# PDB_Supply.net
KiCad netlist of a schematic drawn in Altium Designer
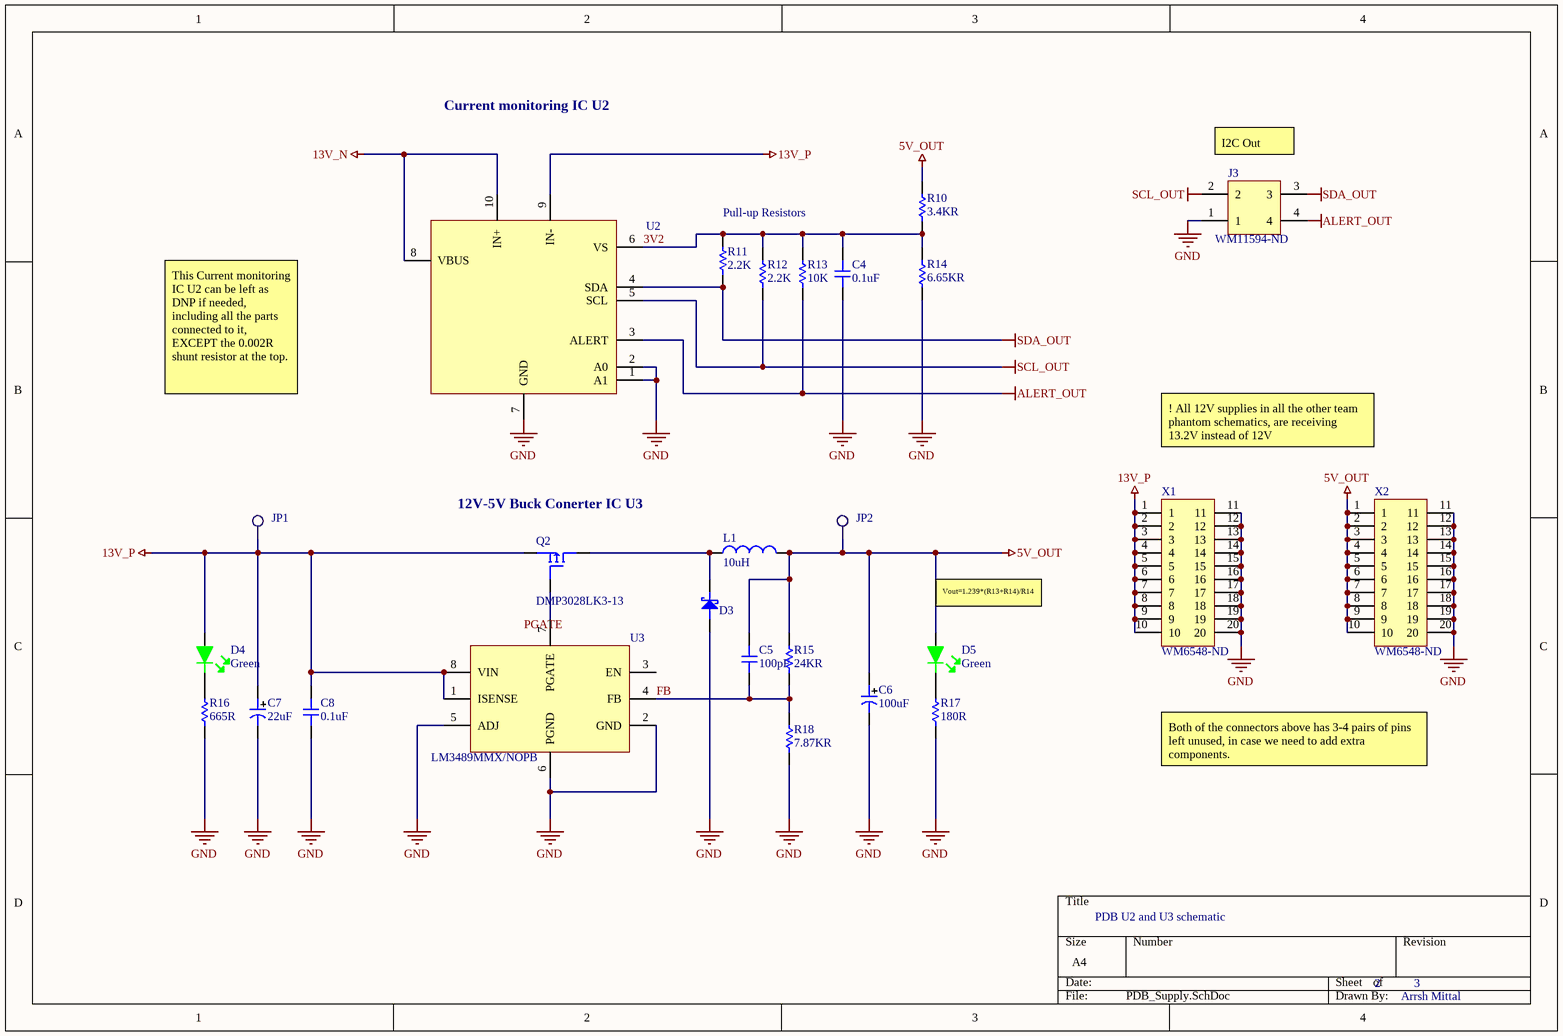
[diagram p0: PDB_Supply.SchDoc]

(export (version "E")
  (design (tool "Eeschema 10.0.6"))
  (components
    (comp (ref "C4")
      (value "0.1uF")
      (footprint "CAP-0805")
      (description "CAP CER 0.1UF 16V Y5V 0805")
      (fields
        (field (name "MANUFACTURER") "KEMET")
        (field (name "MANUFACTURER PART NUMBER") "C0805C104Z4VACTU")
      )
      (libsource (lib "Capacitors") (part "0805-0.1uF-16V"))
    )
    (comp (ref "C5")
      (value "100pF")
      (footprint "CAP-0603")
      (description "0603 100 pF 50 V ±5% Tolerance C0G/NP0 SMT Multilayer Ceramic Capacitor")
      (fields
        (field (name "MANUFACTURER") "Kyocera AVX")
        (field (name "MANUFACTURER PART NUMBER") "06035A101JAT2~{A}4K")
      )
      (libsource (lib "Capacitors") (part "0603-100pF-50V"))
    )
    (comp (ref "C6")
      (value "100uF")
      (footprint "CAPMP7343X31N 2917 Tantilum Cap")
      (fields
        (field (name "MANUFACTURER") "KEMET")
        (field (name "MANUFACTURER PART NUMBER") "T591D107M010ATE080")
        (field (name "TOLERANCE") "20%")
      )
      (libsource (lib "Capacitors") (part "2917-100uF Tantalum Cap"))
    )
    (comp (ref "C7")
      (value "22uF")
      (footprint "CAPAE7366X55M")
      (description "Aluminum Electrolytic Capacitors - SMD 22uF 50 Volts 20% LYTICS/IC")
      (fields
        (field (name "MANUFACTURER") "CDE Illinois Capacitor")
        (field (name "MANUFACTURER PART NUMBER") "226SML050M")
      )
      (libsource (lib "Capacitors") (part "AEC-22uF-50V"))
    )
    (comp (ref "C8")
      (value "0.1uF")
      (footprint "CAP-0805")
      (description "CAP CER 0.1UF 50V Y5V 0805")
      (fields
        (field (name "MANUFACTURER") "KEMET")
        (field (name "MANUFACTURER PART NUMBER") "C0805C104Z5VACTU")
      )
      (libsource (lib "Capacitors") (part "0805-0.1uF-50V"))
    )
    (comp (ref "D3")
      (value "40V")
      (footprint "DO-214AB (SMC)")
      (description "DIODE SCHOTTKY 40V 8A DO214AB")
      (fields (field (name "MANUFACTURER") "MCC") (field (name "MANUFACTURER PART NUMBER") "SK84L-TP"))
      (libsource (lib "Diodes") (part "Schottky-40V-8A"))
    )
    (comp (ref "D4")
      (value "Green")
      (footprint "LED-0603")
      (description "LED GREEN CLEAR 0603 SMD")
      (fields
        (field (name "MANUFACTURER") "Wurth Electronics")
        (field (name "MANUFACTURER PART NUMBER") "150060VS75000")
      )
      (libsource (lib "LEDs") (part "LED-Green"))
    )
    (comp (ref "D5")
      (value "Green")
      (footprint "LED-0603")
      (description "LED GREEN CLEAR 0603 SMD")
      (fields
        (field (name "MANUFACTURER") "Wurth Electronics")
        (field (name "MANUFACTURER PART NUMBER") "150060VS75000")
      )
      (libsource (lib "LEDs") (part "LED-Green"))
    )
    (comp (ref "J3")
      (value "WM11594-ND")
      (footprint "2X2PIN")
      (description "CONN HEADER R/A 4POS 3.5MM")
      (fields (field (name "MANUFACTURER") "Molex") (field (name "MANUFACTURER PART NUMBER") "172316-1104"))
      (libsource (lib "Connectors") (part "2X2PIN"))
    )
    (comp (ref "JP1")
      (value "Testpoint2")
      (footprint "TP2")
      (description "Single layer pad TP")
      (libsource (lib "Misc") (part "Testpoint2"))
    )
    (comp (ref "JP2")
      (value "Testpoint2")
      (footprint "TP2")
      (description "Single layer pad TP")
      (libsource (lib "Misc") (part "Testpoint2"))
    )
    (comp (ref "L1")
      (value "10uH")
      (footprint "PQ2614BLA-100K footprint")
      (description "Inductor Power Shielded Wirewound 10uH 10% 100KHz Ferrite 30A 0.0016Ohm DCR Automotive Tray")
      (fields
        (field (name "MANUFACTURER") "Bourns")
        (field (name "MANUFACTURER PART NUMBER") "PQ2614BLA-100K")
      )
      (libsource (lib "Inductors") (part "10uH-30A"))
    )
    (comp (ref "Q2")
      (value "DMP3028LK3-13")
      (footprint "DPAK229P991X239-3N")
      (description "MOSFET P-CH 30V 27A TO252")
      (fields (field (name "MANUFACTURER") "Diodes"))
      (libsource (lib "PDB_sch_lib") (part "P-FET-30V-27A"))
    )
    (comp (ref "R10")
      (value "3.4KR")
      (footprint "RES-0603")
      (description "Res Thin Film 0603 3.4K Ohm 0.1% 1/10W ±25ppm/°C Molded SMD Paper T/R")
      (fields
        (field (name "MANUFACTURER") "TE Connectivity")
        (field (name "MANUFACTURER PART NUMBER") "RP73PF1J3K4BTDF")
      )
      (libsource (lib "PDB_sch_lib") (part "0603-3.4KR"))
    )
    (comp (ref "R11")
      (value "2.2K")
      (footprint "RES-0603")
      (description "RES SMD 2.2K OHM 1% 1/10W 0603")
      (fields
        (field (name "MANUFACTURER") "Yageo Phycomp")
        (field (name "MANUFACTURER PART NUMBER") "RC0603FR-072K2L")
      )
      (libsource (lib "Resistors") (part "0603-2.2KR"))
    )
    (comp (ref "R12")
      (value "2.2K")
      (footprint "RES-0603")
      (description "RES SMD 2.2K OHM 1% 1/10W 0603")
      (fields
        (field (name "MANUFACTURER") "Yageo Phycomp")
        (field (name "MANUFACTURER PART NUMBER") "RC0603FR-072K2L")
      )
      (libsource (lib "Resistors") (part "0603-2.2KR"))
    )
    (comp (ref "R13")
      (value "10K")
      (footprint "RES-0603")
      (description "RES SMD 10K OHM 5% 1/10W 0603")
      (fields
        (field (name "MANUFACTURER") "Yageo")
        (field (name "MANUFACTURER PART NUMBER") "RC0603JR-0710KL")
      )
      (libsource (lib "Resistors") (part "0603-10KR"))
    )
    (comp (ref "R14")
      (value "6.65KR")
      (footprint "RES-0603")
      (description "RES SMD 6.65K OHM 0.1% 1/6W 0603")
      (fields
        (field (name "MANUFACTURER") "TE Connectivity")
        (field (name "MANUFACTURER PART NUMBER") "8-2176088-4")
      )
      (libsource (lib "PDB_sch_lib") (part "0603-6.65KR"))
    )
    (comp (ref "R15")
      (value "24KR")
      (footprint "RES-0603")
      (description "Res Thick Film 0603 24K Ohm 1% 0.1W(1/10W) ±100ppm/C Molded SMD Automotive Paper T/R")
      (fields
        (field (name "MANUFACTURER") "Vishay")
        (field (name "MANUFACTURER PART NUMBER") "CRCW060324K0FKEA")
      )
      (libsource (lib "PDB_sch_lib") (part "0603-24KR"))
    )
    (comp (ref "R16")
      (value "665R")
      (footprint "RES-0603")
      (description "RES SMD 665 OHM 1% 1/10W 0603")
      (fields
        (field (name "MANUFACTURER") "Yageo")
        (field (name "MANUFACTURER PART NUMBER") "RC0603FR-07665RL")
      )
      (libsource (lib "Resistors") (part "0603-665R"))
    )
    (comp (ref "R17")
      (value "180R")
      (footprint "RES-0603")
      (description "RES SMD 180 OHM 1% 1/10W 0603")
      (fields
        (field (name "MANUFACTURER") "TE Connectivity")
        (field (name "MANUFACTURER PART NUMBER") "CRGCQ0603F180R")
      )
      (libsource (lib "Resistors") (part "0603-180R"))
    )
    (comp (ref "R18")
      (value "7.87KR")
      (footprint "RES-0603")
      (description "RES SMD 7.87K OHM 1% 1/10W 0603")
      (fields
        (field (name "MANUFACTURER") "Vishay")
        (field (name "MANUFACTURER PART NUMBER") "CRCW06037K87FKEA")
      )
      (libsource (lib "PDB_sch_lib") (part "0603-7.87KR"))
    )
    (comp (ref "U2")
      (value "INA226AIDGSR")
      (footprint "10-TFSOP, 10-MSOP INA226")
      (description "Bi Directional Current and Power Monitor 10-Pin VSSOP T/R")
      (fields (field (name "MANUFACTURER") "Texas Instruments"))
      (libsource (lib "PDB_sch_lib") (part "INA226AIDGSR"))
    )
    (comp (ref "U3")
      (value "LM3489MMX/NOPB")
      (footprint "TSOP8-LM3489MMX/NOPB")
      (description "DC DC Cntrlr Single-OUT Buck 4.5V to 35V Input 8-Pin VSSOP T/R")
      (fields (field (name "MANUFACTURER") "TI National Semiconductor"))
      (libsource (lib "ICs") (part "LM3489MMX/NOPB"))
    )
    (comp (ref "X1")
      (value "WM6548-ND")
      (footprint "MOLEX_20pin(RECT)")
      (description "Connector Header Through Hole 20 position 0.100\" (2.54mm)")
      (libsource (lib "Connectors") (part "RECT_MOLEX_20pin"))
    )
    (comp (ref "X2")
      (value "WM6548-ND")
      (footprint "MOLEX_20pin(RECT)")
      (description "Connector Header Through Hole 20 position 0.100\" (2.54mm)")
      (libsource (lib "Connectors") (part "RECT_MOLEX_20pin"))
    )
  )
  (nets
    (net (code "1") (name "/3V2") (class "Default")
      (node (ref "C4") (pin "2") (pinfunction "2_2") (pintype "passive"))
      (node (ref "R10") (pin "1") (pinfunction "1_1") (pintype "passive"))
      (node (ref "R11") (pin "2") (pinfunction "2_2") (pintype "passive"))
      (node (ref "R12") (pin "2") (pinfunction "2_2") (pintype "passive"))
      (node (ref "R13") (pin "2") (pinfunction "2_2") (pintype "passive"))
      (node (ref "R14") (pin "1") (pinfunction "1_1") (pintype "passive"))
      (node (ref "U2") (pin "6") (pinfunction "VS_6") (pintype "power_in"))
    )
    (net (code "3") (name "/FB") (class "Default")
      (node (ref "C5") (pin "1") (pinfunction "1_1") (pintype "passive"))
      (node (ref "R15") (pin "1") (pinfunction "1_1") (pintype "passive"))
      (node (ref "R18") (pin "2") (pinfunction "2_2") (pintype "passive"))
      (node (ref "U3") (pin "4") (pinfunction "FB_4") (pintype "power_in"))
    )
    (net (code "4") (name "5V_OUT") (class "Default")
      (node (ref "C5") (pin "2") (pinfunction "2_2") (pintype "passive"))
      (node (ref "C6") (pin "1") (pinfunction "1_1") (pintype "passive"))
      (node (ref "D5") (pin "1") (pinfunction "1_1") (pintype "passive"))
      (node (ref "JP2") (pin "1") (pinfunction "1_1") (pintype "passive"))
      (node (ref "L1") (pin "2") (pinfunction "2_2") (pintype "passive"))
      (node (ref "R10") (pin "2") (pinfunction "2_2") (pintype "passive"))
      (node (ref "R15") (pin "2") (pinfunction "2_2") (pintype "passive"))
      (node (ref "X2") (pin "1") (pinfunction "1_1") (pintype "passive"))
      (node (ref "X2") (pin "10") (pinfunction "10_10") (pintype "passive"))
      (node (ref "X2") (pin "2") (pinfunction "2_2") (pintype "passive"))
      (node (ref "X2") (pin "3") (pinfunction "3_3") (pintype "passive"))
      (node (ref "X2") (pin "4") (pinfunction "4_4") (pintype "passive"))
      (node (ref "X2") (pin "5") (pinfunction "5_5") (pintype "passive"))
      (node (ref "X2") (pin "6") (pinfunction "6_6") (pintype "passive"))
      (node (ref "X2") (pin "7") (pinfunction "7_7") (pintype "passive"))
      (node (ref "X2") (pin "8") (pinfunction "8_8") (pintype "passive"))
      (node (ref "X2") (pin "9") (pinfunction "9_9") (pintype "passive"))
    )
    (net (code "5") (name "13V_N") (class "Default")
      (node (ref "U2") (pin "10") (pinfunction "IN+_10") (pintype "power_in"))
      (node (ref "U2") (pin "8") (pinfunction "VBUS_8") (pintype "power_in"))
    )
    (net (code "6") (name "13V_P") (class "Default")
      (node (ref "C7") (pin "1") (pinfunction "1_1") (pintype "passive"))
      (node (ref "C8") (pin "2") (pinfunction "2_2") (pintype "passive"))
      (node (ref "D4") (pin "1") (pinfunction "1_1") (pintype "passive"))
      (node (ref "JP1") (pin "1") (pinfunction "1_1") (pintype "passive"))
      (node (ref "Q2") (pin "3") (pinfunction "3_3") (pintype "passive"))
      (node (ref "U2") (pin "9") (pinfunction "IN-_9") (pintype "power_in"))
      (node (ref "U3") (pin "1") (pinfunction "ISENSE_1") (pintype "power_in"))
      (node (ref "U3") (pin "8") (pinfunction "VIN_8") (pintype "power_in"))
      (node (ref "X1") (pin "1") (pinfunction "1_1") (pintype "passive"))
      (node (ref "X1") (pin "10") (pinfunction "10_10") (pintype "passive"))
      (node (ref "X1") (pin "2") (pinfunction "2_2") (pintype "passive"))
      (node (ref "X1") (pin "3") (pinfunction "3_3") (pintype "passive"))
      (node (ref "X1") (pin "4") (pinfunction "4_4") (pintype "passive"))
      (node (ref "X1") (pin "5") (pinfunction "5_5") (pintype "passive"))
      (node (ref "X1") (pin "6") (pinfunction "6_6") (pintype "passive"))
      (node (ref "X1") (pin "7") (pinfunction "7_7") (pintype "passive"))
      (node (ref "X1") (pin "8") (pinfunction "8_8") (pintype "passive"))
      (node (ref "X1") (pin "9") (pinfunction "9_9") (pintype "passive"))
    )
    (net (code "7") (name "ALERT_OUT") (class "Default")
      (node (ref "J3") (pin "4") (pinfunction "4_4") (pintype "passive"))
      (node (ref "R13") (pin "1") (pinfunction "1_1") (pintype "passive"))
      (node (ref "U2") (pin "3") (pinfunction "ALERT_3") (pintype "power_in"))
    )
    (net (code "8") (name "GND") (class "Default")
      (node (ref "C4") (pin "1") (pinfunction "1_1") (pintype "passive"))
      (node (ref "C6") (pin "2") (pinfunction "2_2") (pintype "passive"))
      (node (ref "C7") (pin "2") (pinfunction "2_2") (pintype "passive"))
      (node (ref "C8") (pin "1") (pinfunction "1_1") (pintype "passive"))
      (node (ref "D3") (pin "2") (pinfunction "2_2") (pintype "passive"))
      (node (ref "J3") (pin "1") (pinfunction "1_1") (pintype "passive"))
      (node (ref "R14") (pin "2") (pinfunction "2_2") (pintype "passive"))
      (node (ref "R16") (pin "1") (pinfunction "1_1") (pintype "passive"))
      (node (ref "R17") (pin "1") (pinfunction "1_1") (pintype "passive"))
      (node (ref "R18") (pin "1") (pinfunction "1_1") (pintype "passive"))
      (node (ref "U2") (pin "1") (pinfunction "A1_1") (pintype "power_in"))
      (node (ref "U2") (pin "2") (pinfunction "A0_2") (pintype "power_in"))
      (node (ref "U2") (pin "7") (pinfunction "GND_7") (pintype "power_in"))
      (node (ref "U3") (pin "2") (pinfunction "GND_2") (pintype "power_in"))
      (node (ref "U3") (pin "5") (pinfunction "ADJ_5") (pintype "power_in"))
      (node (ref "U3") (pin "6") (pinfunction "PGND_6") (pintype "power_in"))
      (node (ref "X1") (pin "11") (pinfunction "11_11") (pintype "passive"))
      (node (ref "X1") (pin "12") (pinfunction "12_12") (pintype "passive"))
      (node (ref "X1") (pin "13") (pinfunction "13_13") (pintype "passive"))
      (node (ref "X1") (pin "14") (pinfunction "14_14") (pintype "passive"))
      (node (ref "X1") (pin "15") (pinfunction "15_15") (pintype "passive"))
      (node (ref "X1") (pin "16") (pinfunction "16_16") (pintype "passive"))
      (node (ref "X1") (pin "17") (pinfunction "17_17") (pintype "passive"))
      (node (ref "X1") (pin "18") (pinfunction "18_18") (pintype "passive"))
      (node (ref "X1") (pin "19") (pinfunction "19_19") (pintype "passive"))
      (node (ref "X1") (pin "20") (pinfunction "20_20") (pintype "passive"))
      (node (ref "X2") (pin "11") (pinfunction "11_11") (pintype "passive"))
      (node (ref "X2") (pin "12") (pinfunction "12_12") (pintype "passive"))
      (node (ref "X2") (pin "13") (pinfunction "13_13") (pintype "passive"))
      (node (ref "X2") (pin "14") (pinfunction "14_14") (pintype "passive"))
      (node (ref "X2") (pin "15") (pinfunction "15_15") (pintype "passive"))
      (node (ref "X2") (pin "16") (pinfunction "16_16") (pintype "passive"))
      (node (ref "X2") (pin "17") (pinfunction "17_17") (pintype "passive"))
      (node (ref "X2") (pin "18") (pinfunction "18_18") (pintype "passive"))
      (node (ref "X2") (pin "19") (pinfunction "19_19") (pintype "passive"))
      (node (ref "X2") (pin "20") (pinfunction "20_20") (pintype "passive"))
    )
    (net (code "9") (name "Net-(D3-Pad1)") (class "Default")
      (node (ref "D3") (pin "1") (pinfunction "1_1") (pintype "passive"))
      (node (ref "L1") (pin "1") (pinfunction "1_1") (pintype "passive"))
      (node (ref "Q2") (pin "2") (pinfunction "2_2") (pintype "passive"))
    )
    (net (code "10") (name "Net-(D4-Pad2)") (class "Default")
      (node (ref "D4") (pin "2") (pinfunction "2_2") (pintype "passive"))
      (node (ref "R16") (pin "2") (pinfunction "2_2") (pintype "passive"))
    )
    (net (code "11") (name "Net-(D5-Pad2)") (class "Default")
      (node (ref "D5") (pin "2") (pinfunction "2_2") (pintype "passive"))
      (node (ref "R17") (pin "2") (pinfunction "2_2") (pintype "passive"))
    )
    (net (code "12") (name "Net-(U3-PGATE)") (class "Default")
      (node (ref "Q2") (pin "1") (pinfunction "1_1") (pintype "passive"))
      (node (ref "U3") (pin "7") (pinfunction "PGATE_7") (pintype "power_in"))
    )
    (net (code "13") (name "SCL_OUT") (class "Default")
      (node (ref "J3") (pin "2") (pinfunction "2_2") (pintype "passive"))
      (node (ref "R12") (pin "1") (pinfunction "1_1") (pintype "passive"))
      (node (ref "U2") (pin "5") (pinfunction "SCL_5") (pintype "power_in"))
    )
    (net (code "14") (name "SDA_OUT") (class "Default")
      (node (ref "J3") (pin "3") (pinfunction "3_3") (pintype "passive"))
      (node (ref "R11") (pin "1") (pinfunction "1_1") (pintype "passive"))
      (node (ref "U2") (pin "4") (pinfunction "SDA_4") (pintype "power_in"))
    )
    (net (code "15") (name "unconnected-(U3-EN-Pad3)") (class "Default")
      (node (ref "U3") (pin "3") (pinfunction "EN_3") (pintype "power_in"))
    )
  )
)
